# Mouse-Wheel-SCH.net
KiCad netlist of a schematic drawn in Altium Designer
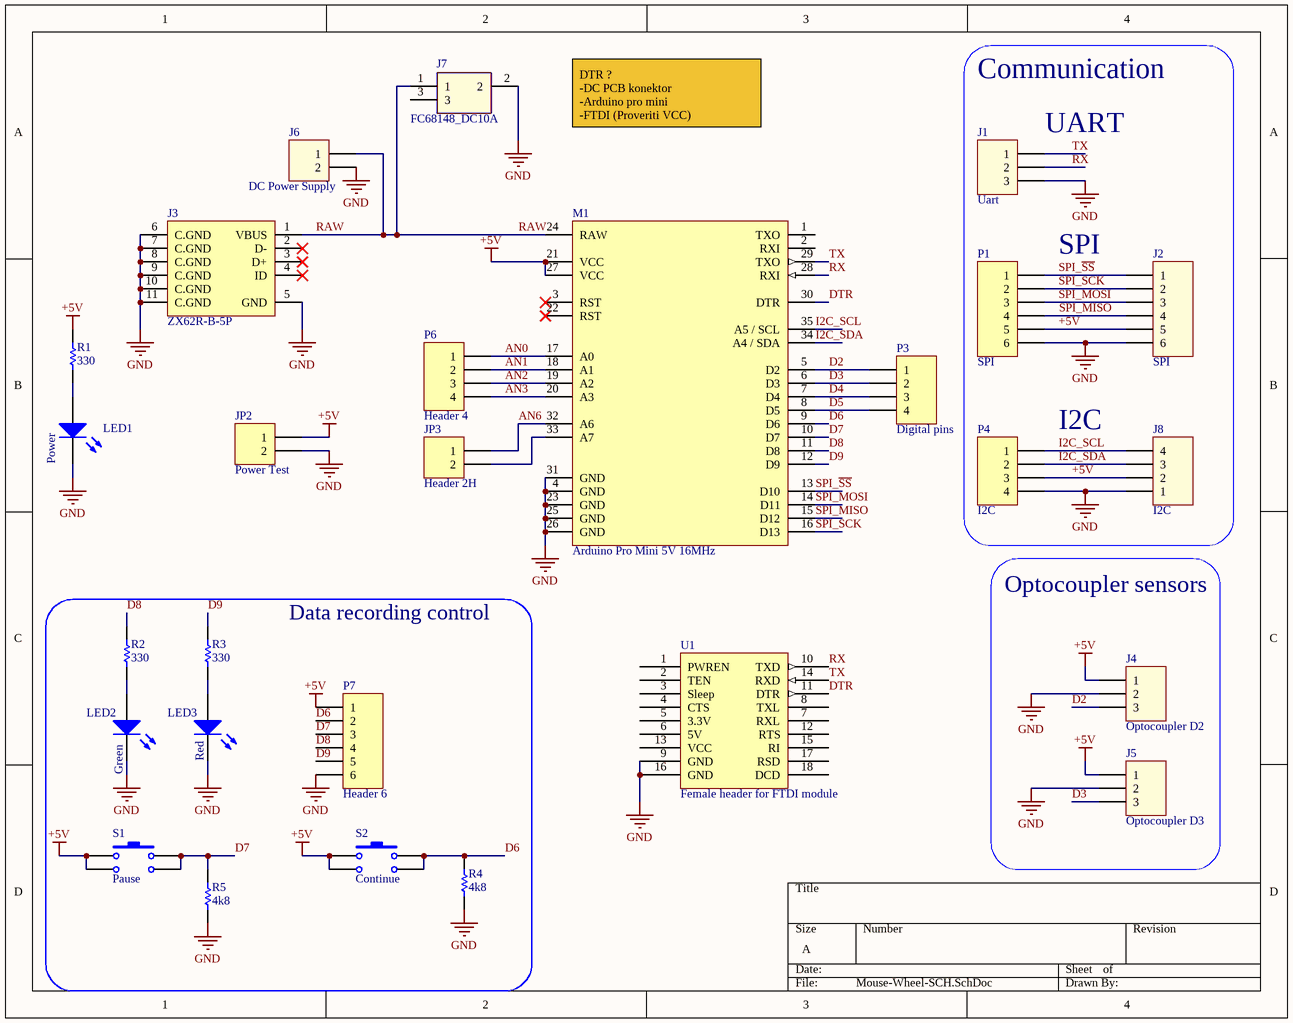
[diagram p0: Mouse-Wheel-SCH.SchDoc]

(export (version "E")
  (design (tool "Eeschema 10.0.6"))
  (components
    (comp (ref "J1")
      (value "Uart")
      (footprint "61900311121")
      (description "WR-WTB 2.54mm Male Locking Header, 3p")
      (fields (field (name "PART NUMBER") "61900311121") (field (name "PUBLISHER") "Wurth Elektronik"))
      (libsource (lib "") (part "61900311121_1"))
    )
    (comp (ref "J2")
      (value "SPI")
      (footprint "61900611021")
      (description "WR-WTB 2.54mm Male Left Angled Header Bottom Locking, 6p")
      (fields (field (name "PART NUMBER") "61900611021") (field (name "PUBLISHER") "Wurth Elektronik"))
      (libsource (lib "ALTIUM-WTB_2_54_MALE_RIGHT_ANGLED_TOP_LOCKING_6190XX19521") (part "61900611021"))
    )
    (comp (ref "J3")
      (value "ZX62R-B-5P")
      (footprint "Micro USB b")
      (description "SMD Micro USB Connector")
      (libsource (lib "KNoT_Thing") (part "ZX62R-B-5P"))
    )
    (comp (ref "J4")
      (value "Optocoupler D2")
      (footprint "61900311121")
      (description "WR-WTB 2.54mm Male Locking Header, 3p")
      (fields (field (name "PART NUMBER") "61900311121") (field (name "PUBLISHER") "Wurth Elektronik"))
      (libsource (lib "ALTIUM-WTB_2_54_MALE_RIGHT_ANGLED_TOP_LOCKING_6190XX19521") (part "61900311121"))
    )
    (comp (ref "J5")
      (value "Optocoupler D3")
      (footprint "61900311121")
      (description "WR-WTB 2.54mm Male Locking Header, 3p")
      (fields (field (name "PART NUMBER") "61900311121") (field (name "PUBLISHER") "Wurth Elektronik"))
      (libsource (lib "ALTIUM-WTB_2_54_MALE_RIGHT_ANGLED_TOP_LOCKING_6190XX19521") (part "61900311121"))
    )
    (comp (ref "J6")
      (value "DC Power Supply")
      (footprint "61900211021")
      (description "WR-WTB 2.54mm Male Left Angled Header Bottom Locking, 2p")
      (fields (field (name "PART NUMBER") "61900211021") (field (name "PUBLISHER") "Wurth Elektronik"))
      (libsource (lib "ALTIUM-WTB_2_54_MALE_RIGHT_ANGLED_TOP_LOCKING_6190XX19521") (part "61900211021"))
    )
    (comp (ref "J7")
      (value "FC68148_DC10A")
      (footprint "FC68148DC10A")
      (description "CLIFF ELECTRONIC COMPONENTS - FC68148 DC10A - SOCKET, PCB, DC POWER, 2.1MM, PK10")
      (fields (field (name "MANUFACTURER_PART_NUMBER") "FC68148 DC10A"))
      (libsource (lib "FC68148_DC10A") (part "FC68148_DC10A"))
    )
    (comp (ref "J8")
      (value "I2C")
      (footprint "61900411021")
      (description "WR-WTB 2.54mm Male Left Angled Header Bottom Locking, 4p")
      (fields (field (name "PART NUMBER") "61900411021") (field (name "PUBLISHER") "Wurth Elektronik"))
      (libsource (lib "ALTIUM-WTB_2_54_MALE_RIGHT_ANGLED_TOP_LOCKING_6190XX19521") (part "61900411021"))
    )
    (comp (ref "JP2")
      (value "Power Test")
      (footprint "HDR1X2")
      (description "Header, 2-Pin, Right Angle")
      (fields (field (name "PUBLISHER") "Altium Limited"))
      (libsource (lib "KNoT_Thing") (part "Header 2H"))
    )
    (comp (ref "JP3")
      (value "Header 2H")
      (footprint "HDR1X2")
      (description "Header, 2-Pin, Right Angle")
      (fields (field (name "PUBLISHER") "Altium Limited"))
      (libsource (lib "KNoT_Thing") (part "Header 2H"))
    )
    (comp (ref "LED1")
      (value "Power")
      (footprint "LED")
      (description "Typical RED, GREEN, YELLOW, AMBER GaAs LED")
      (fields (field (name "PUBLISHER") "Altium Limited"))
      (libsource (lib "KNoT_Thing") (part "LED"))
    )
    (comp (ref "LED2")
      (value "Green")
      (footprint "LED RADIAL 5MM GREEN")
      (description "LED RADIAL")
      (libsource (lib "KNoT-Gateway Library") (part "LED RADIAL 5MM GREEN"))
    )
    (comp (ref "LED3")
      (value "Red")
      (footprint "LED RADIAL 5MM RED")
      (description "LED RADIAL")
      (libsource (lib "KNoT-Gateway Library") (part "LED RADIAL 5MM RED"))
    )
    (comp (ref "M1")
      (value "Arduino Pro Mini 5V 16MHz")
      (footprint "Arduino Pro Mini")
      (libsource (lib "KNoT_Thing") (part "Arduino Pro Mini 5V 16MHz"))
    )
    (comp (ref "P1")
      (value "SPI")
      (footprint "HDR1X6")
      (description "Header, 6-Pin")
      (fields (field (name "PUBLISHER") "Altium Limited"))
      (libsource (lib "") (part "Header 6_1"))
    )
    (comp (ref "P3")
      (value "Digital pins")
      (footprint "HDR1X4")
      (description "Header, 4-Pin")
      (fields (field (name "PUBLISHER") "Altium Limited"))
      (libsource (lib "") (part "Header 4_1"))
    )
    (comp (ref "P4")
      (value "I2C")
      (footprint "HDR1X4")
      (description "Header, 4-Pin")
      (fields (field (name "PUBLISHER") "Altium Limited"))
      (libsource (lib "KNoT_Thing") (part "Header 4"))
    )
    (comp (ref "P6")
      (value "Header 4")
      (footprint "HDR1X4")
      (description "Header, 4-Pin")
      (fields (field (name "PUBLISHER") "Altium Limited"))
      (libsource (lib "KNoT_Thing") (part "Header 4"))
    )
    (comp (ref "P7")
      (value "Header 6")
      (footprint "HDR1X6")
      (description "Header, 6-Pin")
      (fields (field (name "PUBLISHER") "Altium Limited"))
      (libsource (lib "KNoT_Thing") (part "Header 6"))
    )
    (comp (ref "R1")
      (value "330")
      (footprint "AXIAL-3mm")
      (description "Resistor")
      (fields (field (name "PUBLISHER") "Altium Limited"))
      (libsource (lib "KNoT_Thing") (part "Res1"))
    )
    (comp (ref "R2")
      (value "330")
      (footprint "AXIAL-3mm")
      (description "Resistor")
      (fields (field (name "PUBLISHER") "Altium Limited"))
      (libsource (lib "KNoT_Thing") (part "Res1"))
    )
    (comp (ref "R3")
      (value "330")
      (footprint "AXIAL-3mm")
      (description "Resistor")
      (fields (field (name "PUBLISHER") "Altium Limited"))
      (libsource (lib "KNoT_Thing") (part "Res1"))
    )
    (comp (ref "R4")
      (value "4k8")
      (footprint "AXIAL-3mm")
      (description "Resistor")
      (fields (field (name "PUBLISHER") "Altium Limited"))
      (libsource (lib "KNoT_Thing") (part "Res1"))
    )
    (comp (ref "R5")
      (value "4k8")
      (footprint "AXIAL-3mm")
      (description "Resistor")
      (fields (field (name "PUBLISHER") "Altium Limited"))
      (libsource (lib "KNoT_Thing") (part "Res1"))
    )
    (comp (ref "S1")
      (value "Pause")
      (footprint "SW-TACT")
      (description "B3F-1002 SWITCH TACT 6MM MOM 150GF")
      (fields (field (name "PUBLISHER") "Altium Limited"))
      (libsource (lib "KNoT_Thing") (part "SW-PB"))
    )
    (comp (ref "S2")
      (value "Continue")
      (footprint "SW-TACT")
      (description "B3F-1002 SWITCH TACT 6MM MOM 150GF")
      (fields (field (name "PUBLISHER") "Altium Limited"))
      (libsource (lib "KNoT_Thing") (part "SW-PB"))
    )
    (comp (ref "U1")
      (value "Female header for FTDI module")
      (footprint "FTDI_Module")
      (description "Connection header for custom FTDI module")
      (libsource (lib "KNoT_Thing") (part "Module_FTDI"))
    )
  )
  (nets
    (net (code "1") (name "+5V") (class "Default")
      (node (ref "J2") (pin "5") (pinfunction "5_5") (pintype "passive"))
      (node (ref "J4") (pin "1") (pinfunction "1_1") (pintype "passive"))
      (node (ref "J5") (pin "1") (pinfunction "1_1") (pintype "passive"))
      (node (ref "J8") (pin "2") (pinfunction "2_2") (pintype "passive"))
      (node (ref "JP2") (pin "1") (pinfunction "1_1") (pintype "passive"))
      (node (ref "M1") (pin "21") (pinfunction "VCC_21") (pintype "passive"))
      (node (ref "M1") (pin "27") (pinfunction "VCC_27") (pintype "passive"))
      (node (ref "P1") (pin "5") (pinfunction "5_5") (pintype "passive"))
      (node (ref "P4") (pin "3") (pinfunction "3_3") (pintype "passive"))
      (node (ref "P7") (pin "1") (pinfunction "1_1") (pintype "passive"))
      (node (ref "R1") (pin "1") (pinfunction "1_1") (pintype "passive"))
      (node (ref "S1") (pin "1") (pinfunction "1_1") (pintype "passive"))
      (node (ref "S1") (pin "2") (pinfunction "2_2") (pintype "passive"))
      (node (ref "S2") (pin "1") (pinfunction "1_1") (pintype "passive"))
      (node (ref "S2") (pin "2") (pinfunction "2_2") (pintype "passive"))
    )
    (net (code "2") (name "/AN0") (class "Default")
      (node (ref "M1") (pin "17") (pinfunction "A0_17") (pintype "passive"))
      (node (ref "P6") (pin "1") (pinfunction "1_1") (pintype "passive"))
    )
    (net (code "3") (name "/AN1") (class "Default")
      (node (ref "M1") (pin "18") (pinfunction "A1_18") (pintype "passive"))
      (node (ref "P6") (pin "2") (pinfunction "2_2") (pintype "passive"))
    )
    (net (code "4") (name "/AN2") (class "Default")
      (node (ref "M1") (pin "19") (pinfunction "A2_19") (pintype "passive"))
      (node (ref "P6") (pin "3") (pinfunction "3_3") (pintype "passive"))
    )
    (net (code "5") (name "/AN3") (class "Default")
      (node (ref "M1") (pin "20") (pinfunction "A3_20") (pintype "passive"))
      (node (ref "P6") (pin "4") (pinfunction "4_4") (pintype "passive"))
    )
    (net (code "6") (name "/AN6") (class "Default")
      (node (ref "JP3") (pin "1") (pinfunction "1_1") (pintype "passive"))
      (node (ref "M1") (pin "32") (pinfunction "A6_32") (pintype "passive"))
    )
    (net (code "7") (name "/D2") (class "Default")
      (node (ref "J4") (pin "3") (pinfunction "3_3") (pintype "passive"))
      (node (ref "M1") (pin "5") (pinfunction "D2_5") (pintype "passive"))
      (node (ref "P3") (pin "1") (pinfunction "1_1") (pintype "passive"))
    )
    (net (code "8") (name "/D3") (class "Default")
      (node (ref "J5") (pin "3") (pinfunction "3_3") (pintype "passive"))
      (node (ref "M1") (pin "6") (pinfunction "D3_6") (pintype "passive"))
      (node (ref "P3") (pin "2") (pinfunction "2_2") (pintype "passive"))
    )
    (net (code "9") (name "/D4") (class "Default")
      (node (ref "M1") (pin "7") (pinfunction "D4_7") (pintype "passive"))
      (node (ref "P3") (pin "3") (pinfunction "3_3") (pintype "passive"))
    )
    (net (code "10") (name "/D5") (class "Default")
      (node (ref "M1") (pin "8") (pinfunction "D5_8") (pintype "passive"))
      (node (ref "P3") (pin "4") (pinfunction "4_4") (pintype "passive"))
    )
    (net (code "11") (name "/D6") (class "Default")
      (node (ref "M1") (pin "9") (pinfunction "D6_9") (pintype "passive"))
      (node (ref "P7") (pin "2") (pinfunction "2_2") (pintype "passive"))
      (node (ref "R4") (pin "2") (pinfunction "2_2") (pintype "passive"))
      (node (ref "S2") (pin "3") (pinfunction "3_3") (pintype "passive"))
      (node (ref "S2") (pin "4") (pinfunction "4_4") (pintype "passive"))
    )
    (net (code "12") (name "/D7") (class "Default")
      (node (ref "M1") (pin "10") (pinfunction "D7_10") (pintype "passive"))
      (node (ref "P7") (pin "3") (pinfunction "3_3") (pintype "passive"))
      (node (ref "R5") (pin "2") (pinfunction "2_2") (pintype "passive"))
      (node (ref "S1") (pin "3") (pinfunction "3_3") (pintype "passive"))
      (node (ref "S1") (pin "4") (pinfunction "4_4") (pintype "passive"))
    )
    (net (code "13") (name "/D8") (class "Default")
      (node (ref "M1") (pin "11") (pinfunction "D8_11") (pintype "passive"))
      (node (ref "P7") (pin "4") (pinfunction "4_4") (pintype "passive"))
      (node (ref "R2") (pin "1") (pinfunction "1_1") (pintype "passive"))
    )
    (net (code "14") (name "/D9") (class "Default")
      (node (ref "M1") (pin "12") (pinfunction "D9_12") (pintype "passive"))
      (node (ref "P7") (pin "5") (pinfunction "5_5") (pintype "passive"))
      (node (ref "R3") (pin "1") (pinfunction "1_1") (pintype "passive"))
    )
    (net (code "15") (name "/DTR") (class "Default")
      (node (ref "M1") (pin "30") (pinfunction "DTR_30") (pintype "passive"))
      (node (ref "U1") (pin "11") (pinfunction "DTR_11") (pintype "output"))
    )
    (net (code "16") (name "/I2C_SCL") (class "Default")
      (node (ref "J8") (pin "4") (pinfunction "4_4") (pintype "passive"))
      (node (ref "M1") (pin "35") (pinfunction "A5_/_SCL_35") (pintype "passive"))
      (node (ref "P4") (pin "1") (pinfunction "1_1") (pintype "passive"))
    )
    (net (code "17") (name "/I2C_SDA") (class "Default")
      (node (ref "J8") (pin "3") (pinfunction "3_3") (pintype "passive"))
      (node (ref "M1") (pin "34") (pinfunction "A4_/_SDA_34") (pintype "passive"))
      (node (ref "P4") (pin "2") (pinfunction "2_2") (pintype "passive"))
    )
    (net (code "18") (name "/RAW") (class "Default")
      (node (ref "J3") (pin "1") (pinfunction "VBUS_1") (pintype "passive"))
      (node (ref "J6") (pin "1") (pinfunction "1_1") (pintype "passive"))
      (node (ref "J7") (pin "1") (pinfunction "1_1") (pintype "passive"))
      (node (ref "M1") (pin "24") (pinfunction "RAW_24") (pintype "passive"))
    )
    (net (code "19") (name "/RX") (class "Default")
      (node (ref "J1") (pin "2") (pinfunction "2_2") (pintype "passive"))
      (node (ref "M1") (pin "28") (pinfunction "RXI_28") (pintype "input"))
      (node (ref "U1") (pin "10") (pinfunction "TXD_10") (pintype "output"))
    )
    (net (code "20") (name "/SPI_MISO") (class "Default")
      (node (ref "J2") (pin "4") (pinfunction "4_4") (pintype "passive"))
      (node (ref "M1") (pin "15") (pinfunction "D12_15") (pintype "passive"))
      (node (ref "P1") (pin "4") (pinfunction "4_4") (pintype "passive"))
    )
    (net (code "21") (name "/SPI_MOSI") (class "Default")
      (node (ref "J2") (pin "3") (pinfunction "3_3") (pintype "passive"))
      (node (ref "M1") (pin "14") (pinfunction "D11_14") (pintype "passive"))
      (node (ref "P1") (pin "3") (pinfunction "3_3") (pintype "passive"))
    )
    (net (code "22") (name "/SPI_SCK") (class "Default")
      (node (ref "J2") (pin "2") (pinfunction "2_2") (pintype "passive"))
      (node (ref "M1") (pin "16") (pinfunction "D13_16") (pintype "passive"))
      (node (ref "P1") (pin "2") (pinfunction "2_2") (pintype "passive"))
    )
    (net (code "23") (name "/SPI_~{SS}") (class "Default")
      (node (ref "J2") (pin "1") (pinfunction "1_1") (pintype "passive"))
      (node (ref "M1") (pin "13") (pinfunction "D10_13") (pintype "passive"))
      (node (ref "P1") (pin "1") (pinfunction "1_1") (pintype "passive"))
    )
    (net (code "24") (name "/TX") (class "Default")
      (node (ref "J1") (pin "1") (pinfunction "1_1") (pintype "passive"))
      (node (ref "M1") (pin "29") (pinfunction "TXO_29") (pintype "output"))
      (node (ref "U1") (pin "14") (pinfunction "RXD_14") (pintype "input"))
    )
    (net (code "25") (name "GND") (class "Default")
      (node (ref "J1") (pin "3") (pinfunction "3_3") (pintype "passive"))
      (node (ref "J2") (pin "6") (pinfunction "6_6") (pintype "passive"))
      (node (ref "J3") (pin "10") (pinfunction "C.GND_10") (pintype "passive"))
      (node (ref "J3") (pin "11") (pinfunction "C.GND_11") (pintype "passive"))
      (node (ref "J3") (pin "5") (pinfunction "GND_5") (pintype "passive"))
      (node (ref "J3") (pin "6") (pinfunction "C.GND_6") (pintype "passive"))
      (node (ref "J3") (pin "7") (pinfunction "C.GND_7") (pintype "passive"))
      (node (ref "J3") (pin "8") (pinfunction "C.GND_8") (pintype "passive"))
      (node (ref "J3") (pin "9") (pinfunction "C.GND_9") (pintype "passive"))
      (node (ref "J4") (pin "2") (pinfunction "2_2") (pintype "passive"))
      (node (ref "J5") (pin "2") (pinfunction "2_2") (pintype "passive"))
      (node (ref "J6") (pin "2") (pinfunction "2_2") (pintype "passive"))
      (node (ref "J7") (pin "2") (pinfunction "2_2") (pintype "passive"))
      (node (ref "J8") (pin "1") (pinfunction "1_1") (pintype "passive"))
      (node (ref "JP2") (pin "2") (pinfunction "2_2") (pintype "passive"))
      (node (ref "LED1") (pin "2") (pinfunction "K_2") (pintype "passive"))
      (node (ref "LED2") (pin "2") (pinfunction "K_2") (pintype "passive"))
      (node (ref "LED3") (pin "2") (pinfunction "K_2") (pintype "passive"))
      (node (ref "M1") (pin "23") (pinfunction "GND_23") (pintype "passive"))
      (node (ref "M1") (pin "25") (pinfunction "GND_25") (pintype "passive"))
      (node (ref "M1") (pin "26") (pinfunction "GND_26") (pintype "passive"))
      (node (ref "M1") (pin "31") (pinfunction "GND_31") (pintype "passive"))
      (node (ref "M1") (pin "4") (pinfunction "GND_4") (pintype "passive"))
      (node (ref "P1") (pin "6") (pinfunction "6_6") (pintype "passive"))
      (node (ref "P4") (pin "4") (pinfunction "4_4") (pintype "passive"))
      (node (ref "P7") (pin "6") (pinfunction "6_6") (pintype "passive"))
      (node (ref "R4") (pin "1") (pinfunction "1_1") (pintype "passive"))
      (node (ref "R5") (pin "1") (pinfunction "1_1") (pintype "passive"))
      (node (ref "U1") (pin "16") (pinfunction "GND_16") (pintype "passive"))
      (node (ref "U1") (pin "9") (pinfunction "GND_9") (pintype "passive"))
    )
    (net (code "26") (name "Net-(LED1-A)") (class "Default")
      (node (ref "LED1") (pin "1") (pinfunction "A_1") (pintype "passive"))
      (node (ref "R1") (pin "2") (pinfunction "2_2") (pintype "passive"))
    )
    (net (code "27") (name "Net-(LED2-A)") (class "Default")
      (node (ref "LED2") (pin "1") (pinfunction "A_1") (pintype "passive"))
      (node (ref "R2") (pin "2") (pinfunction "2_2") (pintype "passive"))
    )
    (net (code "28") (name "Net-(LED3-A)") (class "Default")
      (node (ref "LED3") (pin "1") (pinfunction "A_1") (pintype "passive"))
      (node (ref "R3") (pin "2") (pinfunction "2_2") (pintype "passive"))
    )
    (net (code "29") (name "Net-(M1-A7)") (class "Default")
      (node (ref "JP3") (pin "2") (pinfunction "2_2") (pintype "passive"))
      (node (ref "M1") (pin "33") (pinfunction "A7_33") (pintype "passive"))
    )
    (net (code "30") (name "unconnected-(J3-D+-Pad3)") (class "Default")
      (node (ref "J3") (pin "3") (pinfunction "D+_3") (pintype "passive+no_connect"))
    )
    (net (code "31") (name "unconnected-(J3-D--Pad2)") (class "Default")
      (node (ref "J3") (pin "2") (pinfunction "D-_2") (pintype "passive+no_connect"))
    )
    (net (code "32") (name "unconnected-(J3-ID-Pad4)") (class "Default")
      (node (ref "J3") (pin "4") (pinfunction "ID_4") (pintype "passive+no_connect"))
    )
    (net (code "33") (name "unconnected-(J7-Pad3)") (class "Default")
      (node (ref "J7") (pin "3") (pinfunction "3_3") (pintype "passive"))
    )
    (net (code "34") (name "unconnected-(M1-RST-Pad3)") (class "Default")
      (node (ref "M1") (pin "3") (pinfunction "RST_3") (pintype "passive+no_connect"))
    )
    (net (code "35") (name "unconnected-(M1-RST-Pad22)") (class "Default")
      (node (ref "M1") (pin "22") (pinfunction "RST_22") (pintype "passive+no_connect"))
    )
    (net (code "36") (name "unconnected-(M1-RXI-Pad2)") (class "Default")
      (node (ref "M1") (pin "2") (pinfunction "RXI_2") (pintype "passive"))
    )
    (net (code "37") (name "unconnected-(M1-TXO-Pad1)") (class "Default")
      (node (ref "M1") (pin "1") (pinfunction "TXO_1") (pintype "passive"))
    )
    (net (code "38") (name "unconnected-(U1-3.3V-Pad5)") (class "Default")
      (node (ref "U1") (pin "5") (pinfunction "3.3V_5") (pintype "passive"))
    )
    (net (code "39") (name "unconnected-(U1-5V-Pad6)") (class "Default")
      (node (ref "U1") (pin "6") (pinfunction "5V_6") (pintype "passive"))
    )
    (net (code "40") (name "unconnected-(U1-CTS-Pad4)") (class "Default")
      (node (ref "U1") (pin "4") (pinfunction "CTS_4") (pintype "passive"))
    )
    (net (code "41") (name "unconnected-(U1-DCD-Pad18)") (class "Default")
      (node (ref "U1") (pin "18") (pinfunction "DCD_18") (pintype "passive"))
    )
    (net (code "42") (name "unconnected-(U1-PWREN-Pad1)") (class "Default")
      (node (ref "U1") (pin "1") (pinfunction "PWREN_1") (pintype "passive"))
    )
    (net (code "43") (name "unconnected-(U1-RI-Pad15)") (class "Default")
      (node (ref "U1") (pin "15") (pinfunction "RI_15") (pintype "passive"))
    )
    (net (code "44") (name "unconnected-(U1-RSD-Pad17)") (class "Default")
      (node (ref "U1") (pin "17") (pinfunction "RSD_17") (pintype "passive"))
    )
    (net (code "45") (name "unconnected-(U1-RTS-Pad12)") (class "Default")
      (node (ref "U1") (pin "12") (pinfunction "RTS_12") (pintype "passive"))
    )
    (net (code "46") (name "unconnected-(U1-RXL-Pad7)") (class "Default")
      (node (ref "U1") (pin "7") (pinfunction "RXL_7") (pintype "passive"))
    )
    (net (code "47") (name "unconnected-(U1-Sleep-Pad3)") (class "Default")
      (node (ref "U1") (pin "3") (pinfunction "Sleep_3") (pintype "passive"))
    )
    (net (code "48") (name "unconnected-(U1-TEN-Pad2)") (class "Default")
      (node (ref "U1") (pin "2") (pinfunction "TEN_2") (pintype "passive"))
    )
    (net (code "49") (name "unconnected-(U1-TXL-Pad8)") (class "Default")
      (node (ref "U1") (pin "8") (pinfunction "TXL_8") (pintype "passive"))
    )
    (net (code "50") (name "unconnected-(U1-VCC-Pad13)") (class "Default")
      (node (ref "U1") (pin "13") (pinfunction "VCC_13") (pintype "passive"))
    )
  )
)
